# SRAM0_-_IS61WV12816DBLL-10BLI.net
KiCad netlist of a schematic drawn in Altium Designer
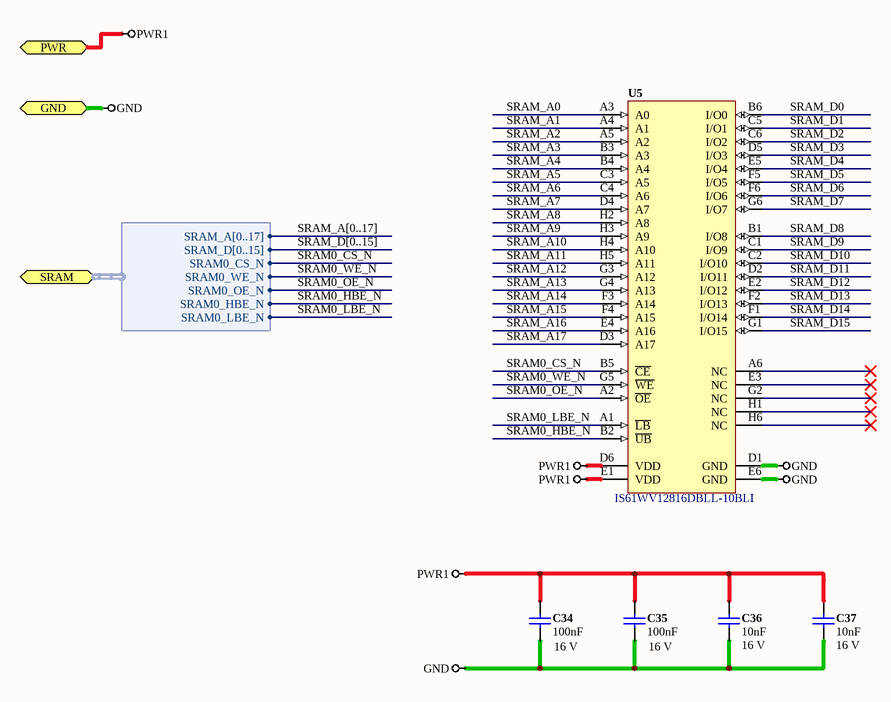
[diagram p0: SRAM0 - IS61WV12816DBLL-10BLI.SchDoc]

(export (version "E")
  (design (tool "Eeschema 10.0.6"))
  (components
    (comp (ref "C34")
      (value "100nF")
      (footprint "CAPC0402(1005)60_L")
      (fields
        (field (name "RATED VOLTAGE") "16 V")
        (field (name "TOLERANCE") "±10%")
        (field (name "MANUFACTURER PART NUMBER") "C0402C104K8PACTU")
        (field (name "Comment") "CAP 100nF 16V 0402(1005)")
      )
      (libsource (lib "Component_Database") (part "CAP_NP"))
    )
    (comp (ref "C35")
      (value "100nF")
      (footprint "CAPC0402(1005)60_L")
      (fields
        (field (name "RATED VOLTAGE") "16 V")
        (field (name "TOLERANCE") "±10%")
        (field (name "MANUFACTURER PART NUMBER") "C0402C104K8PACTU")
        (field (name "Comment") "CAP 100nF 16V 0402(1005)")
      )
      (libsource (lib "Component_Database") (part "CAP_NP"))
    )
    (comp (ref "C36")
      (value "10nF")
      (footprint "CAPC0402(1005)33_L")
      (description "CAP 10nF 16V ±10% 0402 (1005 Metric) Thickness 0.33mm SMD")
      (fields
        (field (name "TOLERANCE") "±10%")
        (field (name "RATED VOLTAGE") "16 V")
        (field (name "MANUFACTURER PART NUMBER") "GRM155R61C103KA01D")
      )
      (libsource (lib "Altium Content Vault") (part "CMP-1034-01875-1"))
    )
    (comp (ref "C37")
      (value "10nF")
      (footprint "CAPC0402(1005)33_L")
      (description "CAP 10nF 16V ±10% 0402 (1005 Metric) Thickness 0.33mm SMD")
      (fields
        (field (name "TOLERANCE") "±10%")
        (field (name "RATED VOLTAGE") "16 V")
        (field (name "MANUFACTURER PART NUMBER") "GRM155R61C103KA01D")
      )
      (libsource (lib "Altium Content Vault") (part "CMP-1034-01875-1"))
    )
    (comp (ref "U5")
      (value "IS61WV12816DBLL-10BLI")
      (footprint "ISSI-TF-BGA-48-6000X8000DE")
      (description "2 M High Speed Asynchronous CMOS SRAM, 128 K x 16, -40 to 85 degC, 48-Pin BGA (TF-BGA-48), Pb-Free")
      (fields (field (name "MANUFACTURER") "Integrated Silicon Solution Inc (ISSI)"))
      (libsource (lib "Altium Content Vault") (part "ISSI-IS61WV12816DALL_DBLL-TF-BGA-48"))
    )
  )
  (nets
    (net (code "2") (name "/SRAM0_CS_N") (class "Default")
      (node (ref "U5") (pin "B5") (pinfunction "~{CE}_B5") (pintype "input"))
    )
    (net (code "3") (name "/SRAM0_HBE_N") (class "Default")
      (node (ref "U5") (pin "B2") (pinfunction "~{UB}_B2") (pintype "input"))
    )
    (net (code "4") (name "/SRAM0_LBE_N") (class "Default")
      (node (ref "U5") (pin "A1") (pinfunction "~{LB}_A1") (pintype "input"))
    )
    (net (code "5") (name "/SRAM0_OE_N") (class "Default")
      (node (ref "U5") (pin "A2") (pinfunction "~{OE}_A2") (pintype "input"))
    )
    (net (code "6") (name "/SRAM0_WE_N") (class "Default")
      (node (ref "U5") (pin "G5") (pinfunction "~{WE}_G5") (pintype "input"))
    )
    (net (code "7") (name "/SRAM_A0") (class "Default")
      (node (ref "U5") (pin "A3") (pinfunction "A0_A3") (pintype "input"))
    )
    (net (code "8") (name "/SRAM_A1") (class "Default")
      (node (ref "U5") (pin "A4") (pinfunction "A1_A4") (pintype "input"))
    )
    (net (code "9") (name "/SRAM_A2") (class "Default")
      (node (ref "U5") (pin "A5") (pinfunction "A2_A5") (pintype "input"))
    )
    (net (code "10") (name "/SRAM_A3") (class "Default")
      (node (ref "U5") (pin "B3") (pinfunction "A3_B3") (pintype "input"))
    )
    (net (code "11") (name "/SRAM_A4") (class "Default")
      (node (ref "U5") (pin "B4") (pinfunction "A4_B4") (pintype "input"))
    )
    (net (code "12") (name "/SRAM_A5") (class "Default")
      (node (ref "U5") (pin "C3") (pinfunction "A5_C3") (pintype "input"))
    )
    (net (code "13") (name "/SRAM_A6") (class "Default")
      (node (ref "U5") (pin "C4") (pinfunction "A6_C4") (pintype "input"))
    )
    (net (code "14") (name "/SRAM_A7") (class "Default")
      (node (ref "U5") (pin "D4") (pinfunction "A7_D4") (pintype "input"))
    )
    (net (code "15") (name "/SRAM_A8") (class "Default")
      (node (ref "U5") (pin "H2") (pinfunction "A8_H2") (pintype "input"))
    )
    (net (code "16") (name "/SRAM_A9") (class "Default")
      (node (ref "U5") (pin "H3") (pinfunction "A9_H3") (pintype "input"))
    )
    (net (code "17") (name "/SRAM_A10") (class "Default")
      (node (ref "U5") (pin "H4") (pinfunction "A10_H4") (pintype "input"))
    )
    (net (code "18") (name "/SRAM_A11") (class "Default")
      (node (ref "U5") (pin "H5") (pinfunction "A11_H5") (pintype "input"))
    )
    (net (code "19") (name "/SRAM_A12") (class "Default")
      (node (ref "U5") (pin "G3") (pinfunction "A12_G3") (pintype "input"))
    )
    (net (code "20") (name "/SRAM_A13") (class "Default")
      (node (ref "U5") (pin "G4") (pinfunction "A13_G4") (pintype "input"))
    )
    (net (code "21") (name "/SRAM_A14") (class "Default")
      (node (ref "U5") (pin "F3") (pinfunction "A14_F3") (pintype "input"))
    )
    (net (code "22") (name "/SRAM_A15") (class "Default")
      (node (ref "U5") (pin "F4") (pinfunction "A15_F4") (pintype "input"))
    )
    (net (code "23") (name "/SRAM_A16") (class "Default")
      (node (ref "U5") (pin "E4") (pinfunction "A16_E4") (pintype "input"))
    )
    (net (code "24") (name "/SRAM_A17") (class "Default")
      (node (ref "U5") (pin "D3") (pinfunction "A17_D3") (pintype "input"))
    )
    (net (code "26") (name "/SRAM_D0") (class "Default")
      (node (ref "U5") (pin "B6") (pinfunction "I/O0_B6") (pintype "bidirectional"))
    )
    (net (code "27") (name "/SRAM_D1") (class "Default")
      (node (ref "U5") (pin "C5") (pinfunction "I/O1_C5") (pintype "bidirectional"))
    )
    (net (code "28") (name "/SRAM_D2") (class "Default")
      (node (ref "U5") (pin "C6") (pinfunction "I/O2_C6") (pintype "bidirectional"))
    )
    (net (code "29") (name "/SRAM_D3") (class "Default")
      (node (ref "U5") (pin "D5") (pinfunction "I/O3_D5") (pintype "bidirectional"))
    )
    (net (code "30") (name "/SRAM_D4") (class "Default")
      (node (ref "U5") (pin "E5") (pinfunction "I/O4_E5") (pintype "bidirectional"))
    )
    (net (code "31") (name "/SRAM_D5") (class "Default")
      (node (ref "U5") (pin "F5") (pinfunction "I/O5_F5") (pintype "bidirectional"))
    )
    (net (code "32") (name "/SRAM_D6") (class "Default")
      (node (ref "U5") (pin "F6") (pinfunction "I/O6_F6") (pintype "bidirectional"))
    )
    (net (code "33") (name "/SRAM_D7") (class "Default")
      (node (ref "U5") (pin "G6") (pinfunction "I/O7_G6") (pintype "bidirectional"))
    )
    (net (code "34") (name "/SRAM_D8") (class "Default")
      (node (ref "U5") (pin "B1") (pinfunction "I/O8_B1") (pintype "bidirectional"))
    )
    (net (code "35") (name "/SRAM_D9") (class "Default")
      (node (ref "U5") (pin "C1") (pinfunction "I/O9_C1") (pintype "bidirectional"))
    )
    (net (code "36") (name "/SRAM_D10") (class "Default")
      (node (ref "U5") (pin "C2") (pinfunction "I/O10_C2") (pintype "bidirectional"))
    )
    (net (code "37") (name "/SRAM_D11") (class "Default")
      (node (ref "U5") (pin "D2") (pinfunction "I/O11_D2") (pintype "bidirectional"))
    )
    (net (code "38") (name "/SRAM_D12") (class "Default")
      (node (ref "U5") (pin "E2") (pinfunction "I/O12_E2") (pintype "bidirectional"))
    )
    (net (code "39") (name "/SRAM_D13") (class "Default")
      (node (ref "U5") (pin "F2") (pinfunction "I/O13_F2") (pintype "bidirectional"))
    )
    (net (code "40") (name "/SRAM_D14") (class "Default")
      (node (ref "U5") (pin "F1") (pinfunction "I/O14_F1") (pintype "bidirectional"))
    )
    (net (code "41") (name "/SRAM_D15") (class "Default")
      (node (ref "U5") (pin "G1") (pinfunction "I/O15_G1") (pintype "bidirectional"))
    )
    (net (code "44") (name "GND") (class "Default")
      (node (ref "C34") (pin "2") (pinfunction "2_2") (pintype "passive"))
      (node (ref "C35") (pin "2") (pinfunction "2_2") (pintype "passive"))
      (node (ref "C36") (pin "2") (pinfunction "2_2") (pintype "passive"))
      (node (ref "C37") (pin "2") (pinfunction "2_2") (pintype "passive"))
      (node (ref "U5") (pin "D1") (pinfunction "GND_D1") (pintype "power_in"))
      (node (ref "U5") (pin "E6") (pinfunction "GND_E6") (pintype "power_in"))
    )
    (net (code "45") (name "PWR1") (class "Default")
      (node (ref "C34") (pin "1") (pinfunction "1_1") (pintype "passive"))
      (node (ref "C35") (pin "1") (pinfunction "1_1") (pintype "passive"))
      (node (ref "C36") (pin "1") (pinfunction "1_1") (pintype "passive"))
      (node (ref "C37") (pin "1") (pinfunction "1_1") (pintype "passive"))
      (node (ref "U5") (pin "D6") (pinfunction "VDD_D6") (pintype "power_in"))
      (node (ref "U5") (pin "E1") (pinfunction "VDD_E1") (pintype "power_in"))
    )
    (net (code "46") (name "unconnected-(U5-NC-PadA6)") (class "Default")
      (node (ref "U5") (pin "A6") (pinfunction "NC_A6") (pintype "passive+no_connect"))
    )
    (net (code "47") (name "unconnected-(U5-NC-PadE3)") (class "Default")
      (node (ref "U5") (pin "E3") (pinfunction "NC_E3") (pintype "passive+no_connect"))
    )
    (net (code "48") (name "unconnected-(U5-NC-PadG2)") (class "Default")
      (node (ref "U5") (pin "G2") (pinfunction "NC_G2") (pintype "passive+no_connect"))
    )
    (net (code "49") (name "unconnected-(U5-NC-PadH1)") (class "Default")
      (node (ref "U5") (pin "H1") (pinfunction "NC_H1") (pintype "passive+no_connect"))
    )
    (net (code "50") (name "unconnected-(U5-NC-PadH6)") (class "Default")
      (node (ref "U5") (pin "H6") (pinfunction "NC_H6") (pintype "passive+no_connect"))
    )
  )
)
